# Simulation_PFC.net
KiCad netlist of a schematic drawn in Altium Designer
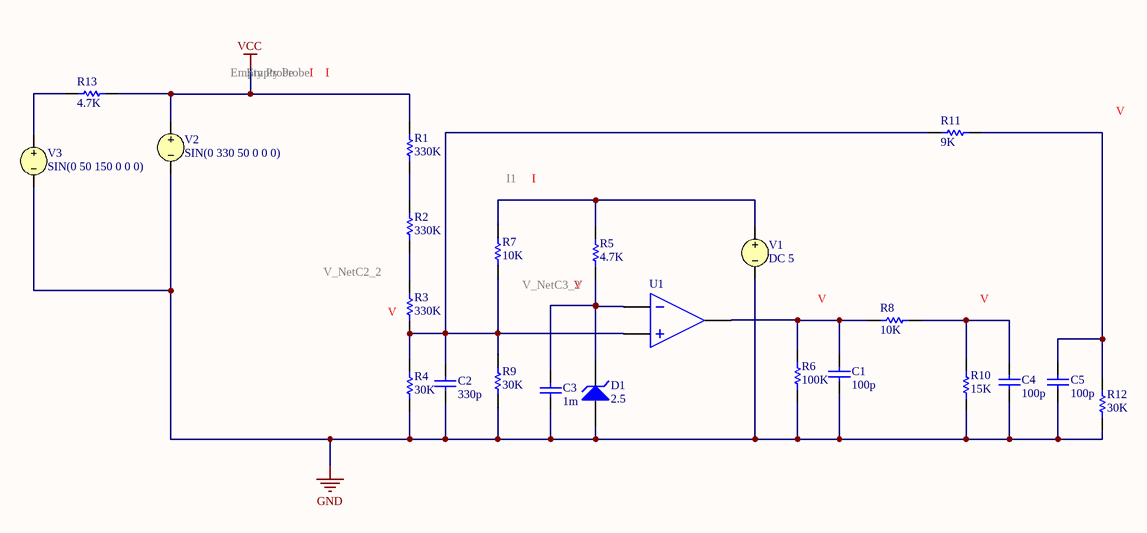
[diagram p0: Simulation_PFC.SchDoc]

(export (version "E")
  (design (tool "Eeschema 10.0.6"))
  (components
    (comp (ref "C1")
      (value "100p")
      (description "Capacitor")
      (libsource (lib "Simulation Generic Components") (part "Capacitor"))
    )
    (comp (ref "C2")
      (value "330p")
      (description "Capacitor")
      (libsource (lib "Simulation Generic Components") (part "Capacitor"))
    )
    (comp (ref "C3")
      (value "1m")
      (description "Capacitor")
      (libsource (lib "Simulation Generic Components") (part "Capacitor"))
    )
    (comp (ref "C4")
      (value "100p")
      (description "Capacitor")
      (libsource (lib "Simulation Generic Components") (part "Capacitor"))
    )
    (comp (ref "C5")
      (value "100p")
      (description "Capacitor")
      (libsource (lib "Simulation Generic Components") (part "Capacitor"))
    )
    (comp (ref "D1")
      (value "Zener Diode")
      (fields (field (name "BV") "2.5"))
      (libsource (lib "Simulation Generic Components") (part "Zener Diode"))
    )
    (comp (ref "R1")
      (value "330K")
      (description "Resistor")
      (libsource (lib "Simulation Generic Components") (part "Resistor"))
    )
    (comp (ref "R2")
      (value "330K")
      (description "Resistor")
      (libsource (lib "Simulation Generic Components") (part "Resistor"))
    )
    (comp (ref "R3")
      (value "330K")
      (description "Resistor")
      (libsource (lib "Simulation Generic Components") (part "Resistor"))
    )
    (comp (ref "R4")
      (value "30K")
      (description "Resistor")
      (libsource (lib "Simulation Generic Components") (part "Resistor"))
    )
    (comp (ref "R5")
      (value "4.7K")
      (description "Resistor")
      (libsource (lib "Simulation Generic Components") (part "Resistor"))
    )
    (comp (ref "R6")
      (value "100K")
      (description "Resistor")
      (libsource (lib "Simulation Generic Components") (part "Resistor"))
    )
    (comp (ref "R7")
      (value "10K")
      (description "Resistor")
      (libsource (lib "Simulation Generic Components") (part "Resistor"))
    )
    (comp (ref "R8")
      (value "10K")
      (description "Resistor")
      (libsource (lib "Simulation Generic Components") (part "Resistor"))
    )
    (comp (ref "R9")
      (value "30K")
      (description "Resistor")
      (libsource (lib "Simulation Generic Components") (part "Resistor"))
    )
    (comp (ref "R10")
      (value "15K")
      (description "Resistor")
      (libsource (lib "Simulation Generic Components") (part "Resistor"))
    )
    (comp (ref "R11")
      (value "9K")
      (description "Resistor")
      (libsource (lib "Simulation Generic Components") (part "Resistor"))
    )
    (comp (ref "R12")
      (value "30K")
      (description "Resistor")
      (libsource (lib "Simulation Generic Components") (part "Resistor"))
    )
    (comp (ref "R13")
      (value "4.7K")
      (description "Resistor")
      (libsource (lib "Simulation Generic Components") (part "Resistor"))
    )
    (comp (ref "U1")
      (value "Ideal Comparator")
      (libsource (lib "Simulation Generic Components") (part "Comparator"))
    )
    (comp (ref "V1")
      (value "DC 5")
      (description "Voltage Source")
      (fields (field (name "PUBLISHER") "Altium Limited"))
      (libsource (lib "Simulation Generic Components") (part "VSRC"))
    )
    (comp (ref "V2")
      (value "SIN(0 330 50 0 0 0)")
      (description "Voltage Source")
      (fields (field (name "PUBLISHER") "Altium Limited"))
      (libsource (lib "Simulation Generic Components") (part "VSRC"))
    )
    (comp (ref "V3")
      (value "SIN(0 50 150 0 0 0)")
      (description "Voltage Source")
      (fields (field (name "PUBLISHER") "Altium Limited"))
      (libsource (lib "Simulation Generic Components") (part "VSRC"))
    )
  )
  (nets
    (net (code "1") (name "GND") (class "Default")
      (node (ref "C1") (pin "1") (pinfunction "1_1") (pintype "passive"))
      (node (ref "C2") (pin "1") (pinfunction "1_1") (pintype "passive"))
      (node (ref "C3") (pin "1") (pinfunction "1_1") (pintype "passive"))
      (node (ref "C4") (pin "1") (pinfunction "1_1") (pintype "passive"))
      (node (ref "C5") (pin "1") (pinfunction "1_1") (pintype "passive"))
      (node (ref "D1") (pin "1") (pinfunction "A_1") (pintype "passive"))
      (node (ref "R10") (pin "1") (pinfunction "1_1") (pintype "passive"))
      (node (ref "R12") (pin "1") (pinfunction "1_1") (pintype "passive"))
      (node (ref "R4") (pin "1") (pinfunction "1_1") (pintype "passive"))
      (node (ref "R6") (pin "1") (pinfunction "1_1") (pintype "passive"))
      (node (ref "R9") (pin "1") (pinfunction "1_1") (pintype "passive"))
      (node (ref "V1") (pin "2") (pinfunction "2_2") (pintype "passive"))
      (node (ref "V2") (pin "2") (pinfunction "2_2") (pintype "passive"))
      (node (ref "V3") (pin "2") (pinfunction "2_2") (pintype "passive"))
    )
    (net (code "2") (name "Net-(C4-Pad2)") (class "Default")
      (node (ref "C4") (pin "2") (pinfunction "2_2") (pintype "passive"))
      (node (ref "R10") (pin "2") (pinfunction "2_2") (pintype "passive"))
      (node (ref "R8") (pin "1") (pinfunction "1_1") (pintype "passive"))
    )
    (net (code "3") (name "Net-(C5-Pad2)") (class "Default")
      (node (ref "C5") (pin "2") (pinfunction "2_2") (pintype "passive"))
      (node (ref "R11") (pin "1") (pinfunction "1_1") (pintype "passive"))
      (node (ref "R12") (pin "2") (pinfunction "2_2") (pintype "passive"))
    )
    (net (code "4") (name "Net-(D1-K)") (class "Default")
      (node (ref "C3") (pin "2") (pinfunction "2_2") (pintype "passive"))
      (node (ref "D1") (pin "2") (pinfunction "K_2") (pintype "passive"))
      (node (ref "R5") (pin "1") (pinfunction "1_1") (pintype "passive"))
      (node (ref "U1") (pin "1") (pinfunction "IN-_1") (pintype "passive"))
    )
    (net (code "5") (name "Net-(R1-Pad1)") (class "Default")
      (node (ref "R1") (pin "1") (pinfunction "1_1") (pintype "passive"))
      (node (ref "R2") (pin "2") (pinfunction "2_2") (pintype "passive"))
    )
    (net (code "6") (name "Net-(R2-Pad1)") (class "Default")
      (node (ref "R2") (pin "1") (pinfunction "1_1") (pintype "passive"))
      (node (ref "R3") (pin "2") (pinfunction "2_2") (pintype "passive"))
    )
    (net (code "7") (name "Net-(R5-Pad2)") (class "Default")
      (node (ref "R5") (pin "2") (pinfunction "2_2") (pintype "passive"))
      (node (ref "R7") (pin "2") (pinfunction "2_2") (pintype "passive"))
      (node (ref "V1") (pin "1") (pinfunction "1_1") (pintype "passive"))
    )
    (net (code "8") (name "Net-(R13-Pad2)") (class "Default")
      (node (ref "R13") (pin "2") (pinfunction "2_2") (pintype "passive"))
      (node (ref "V3") (pin "1") (pinfunction "1_1") (pintype "passive"))
    )
    (net (code "9") (name "Net-(U1-IN+)") (class "Default")
      (node (ref "C2") (pin "2") (pinfunction "2_2") (pintype "passive"))
      (node (ref "R11") (pin "2") (pinfunction "2_2") (pintype "passive"))
      (node (ref "R3") (pin "1") (pinfunction "1_1") (pintype "passive"))
      (node (ref "R4") (pin "2") (pinfunction "2_2") (pintype "passive"))
      (node (ref "R7") (pin "1") (pinfunction "1_1") (pintype "passive"))
      (node (ref "R9") (pin "2") (pinfunction "2_2") (pintype "passive"))
      (node (ref "U1") (pin "2") (pinfunction "IN+_2") (pintype "passive"))
    )
    (net (code "10") (name "Net-(U1-OUT)") (class "Default")
      (node (ref "C1") (pin "2") (pinfunction "2_2") (pintype "passive"))
      (node (ref "R6") (pin "2") (pinfunction "2_2") (pintype "passive"))
      (node (ref "R8") (pin "2") (pinfunction "2_2") (pintype "passive"))
      (node (ref "U1") (pin "3") (pinfunction "OUT_3") (pintype "passive"))
    )
    (net (code "11") (name "VCC") (class "Default")
      (node (ref "R1") (pin "2") (pinfunction "2_2") (pintype "passive"))
      (node (ref "R13") (pin "1") (pinfunction "1_1") (pintype "passive"))
      (node (ref "V2") (pin "1") (pinfunction "1_1") (pintype "passive"))
    )
  )
)
